# weft-microboard-0.net
KiCad netlist of a schematic drawn in EAGLE
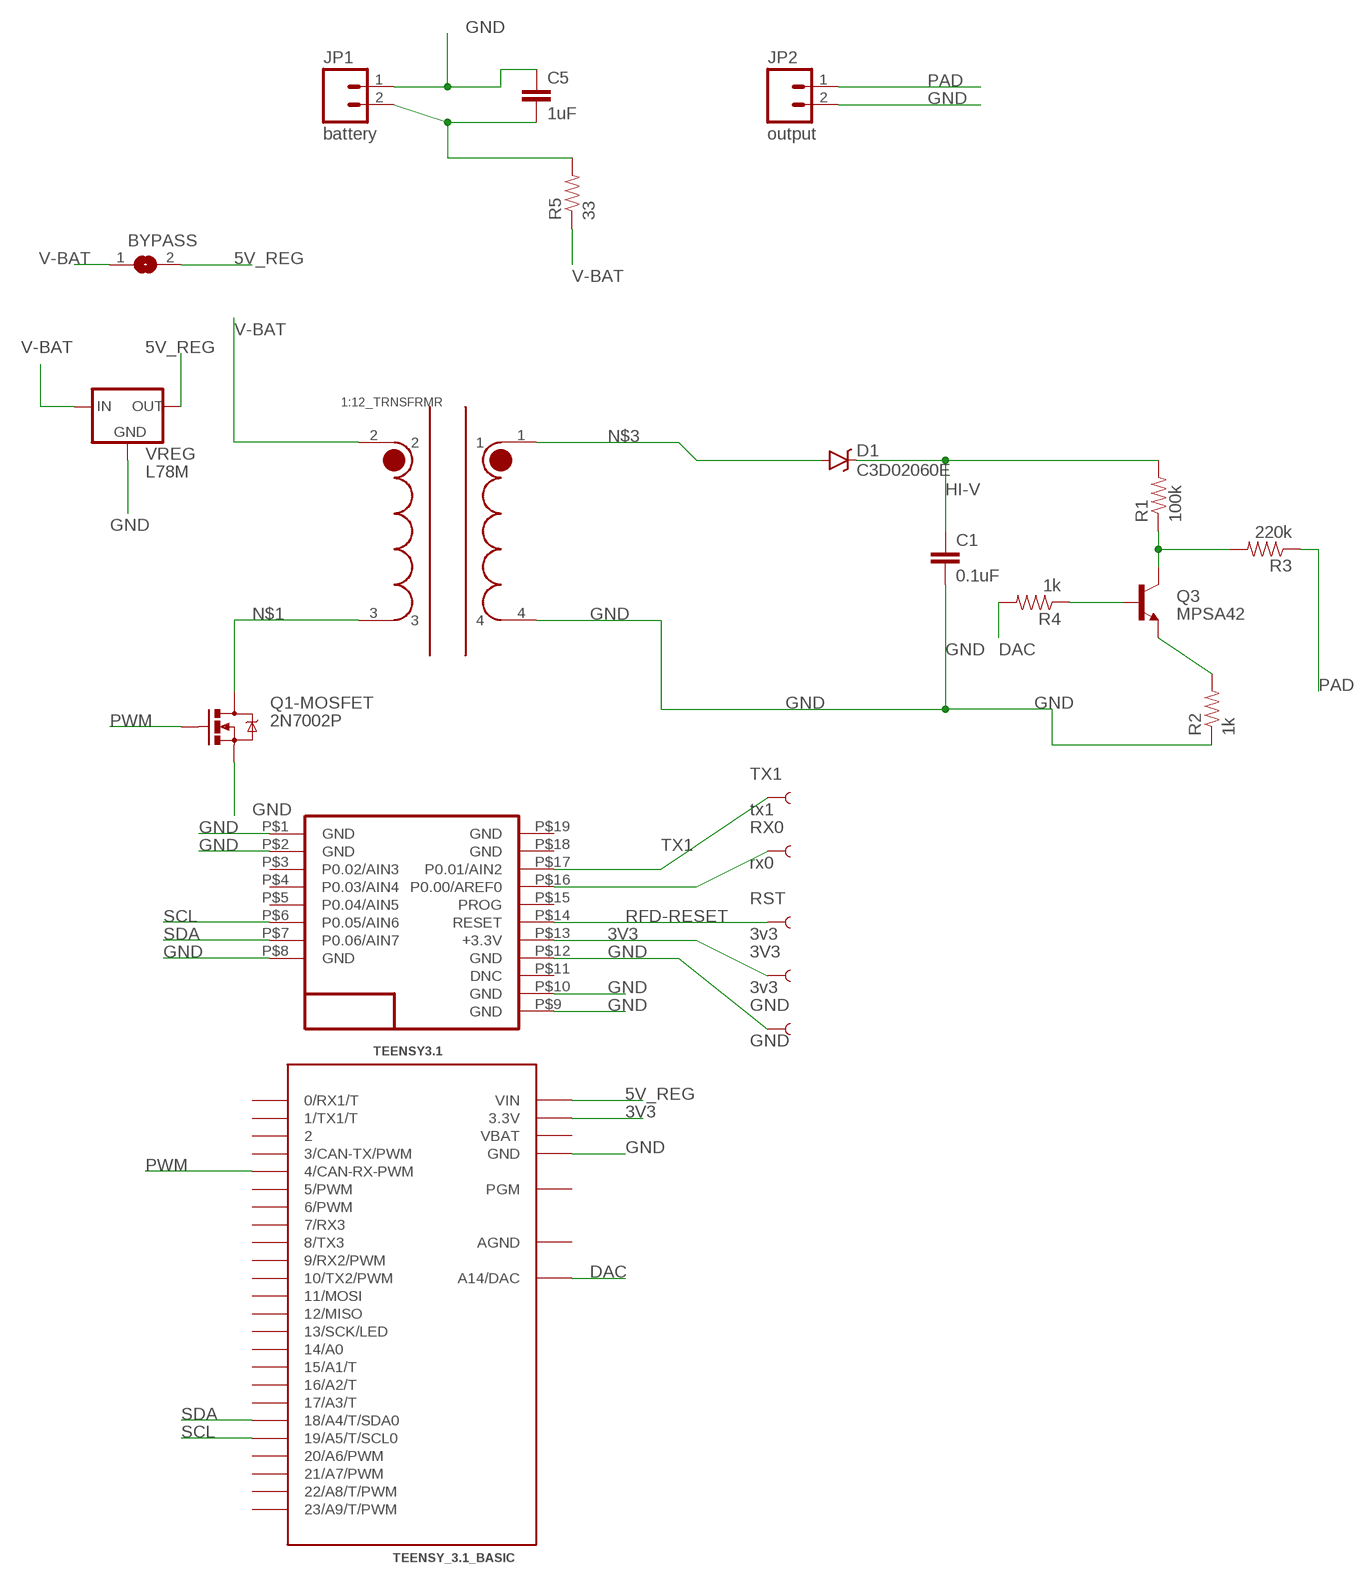
[diagram p0: schematic, sheet 1]

(export (version "E")
  (design (tool "Eeschema 10.0.6"))
  (components
    (comp (ref "1:12_TRNSFRMR")
      (value "PA0367")
      (footprint "eagle-import:PA0367")
      (libsource (lib "eagle-import") (part "PA0367"))
    )
    (comp (ref "3V3")
      (value "3v3")
      (footprint "eagle-import:PAD.03X.03")
      (libsource (lib "eagle-import") (part "TEST-POINT3"))
    )
    (comp (ref "BYPASS")
      (value "SJ")
      (footprint "eagle-import:SJ")
      (libsource (lib "eagle-import") (part "SJ"))
    )
    (comp (ref "C1")
      (value "0.1uF")
      (footprint "eagle-import:0805")
      (libsource (lib "eagle-import") (part "SparkFun-Passives_CAP0805"))
    )
    (comp (ref "C5")
      (value "1uF")
      (footprint "eagle-import:0805")
      (libsource (lib "eagle-import") (part "CAP0805"))
    )
    (comp (ref "D1")
      (value "C3D02060E")
      (footprint "eagle-import:TO252")
      (libsource (lib "eagle-import") (part "C3D02060E"))
    )
    (comp (ref "GND")
      (value "GND")
      (footprint "eagle-import:PAD.03X.03")
      (libsource (lib "eagle-import") (part "TEST-POINT3"))
    )
    (comp (ref "JP1")
      (value "battery")
      (footprint "eagle-import:JST-2-SMD")
      (libsource (lib "eagle-import") (part "M02-JST-2MM-SMT"))
    )
    (comp (ref "JP2")
      (value "output")
      (footprint "eagle-import:JST-2-SMD")
      (libsource (lib "eagle-import") (part "M02-JST-2MM-SMT"))
    )
    (comp (ref "Q1-MOSFET")
      (value "2N7002P")
      (footprint "eagle-import:SOT23-3")
      (libsource (lib "eagle-import") (part "MOSFET-NCHANNELBSS123LT1G"))
    )
    (comp (ref "Q3")
      (value "MPSA42")
      (footprint "eagle-import:SOT23-3")
      (libsource (lib "eagle-import") (part "TRANSISTOR_NPNMPSA42"))
    )
    (comp (ref "R1")
      (value "100k")
      (footprint "eagle-import:1206")
      (libsource (lib "eagle-import") (part "RESISTOR1206"))
    )
    (comp (ref "R2")
      (value "1k")
      (footprint "eagle-import:0805")
      (libsource (lib "eagle-import") (part "RESISTOR0805-RES"))
    )
    (comp (ref "R3")
      (value "220k")
      (footprint "eagle-import:1206")
      (libsource (lib "eagle-import") (part "RESISTOR1206"))
    )
    (comp (ref "R4")
      (value "1k")
      (footprint "eagle-import:0805")
      (libsource (lib "eagle-import") (part "RESISTOR0805-RES"))
    )
    (comp (ref "R5")
      (value "33")
      (footprint "eagle-import:0805")
      (libsource (lib "eagle-import") (part "RESISTOR0805-RES"))
    )
    (comp (ref "RFDUINO")
      (value "RFD22301")
      (footprint "eagle-import:RFD21733")
      (libsource (lib "eagle-import") (part "RFD22301"))
    )
    (comp (ref "RST")
      (value "3v3")
      (footprint "eagle-import:PAD.03X.03")
      (libsource (lib "eagle-import") (part "TEST-POINT3"))
    )
    (comp (ref "RX0")
      (value "rx0")
      (footprint "eagle-import:PAD.03X.03")
      (libsource (lib "eagle-import") (part "TEST-POINT3"))
    )
    (comp (ref "TEENSY3.1")
      (value "TEENSY_3.1_BASIC")
      (footprint "eagle-import:TEENSY_3.1_BASIC")
      (libsource (lib "eagle-import") (part "TEENSY_3.1_BASIC"))
    )
    (comp (ref "TX1")
      (value "tx1")
      (footprint "eagle-import:PAD.03X.03")
      (libsource (lib "eagle-import") (part "TEST-POINT3"))
    )
    (comp (ref "VREG")
      (value "L78M")
      (footprint "eagle-import:DPAK")
      (libsource (lib "eagle-import") (part "L78M"))
    )
  )
  (nets
    (net (code "1") (name "/3V3") (class "Default")
      (node (ref "3V3") (pin "P$1") (pinfunction "1_P$1") (pintype "bidirectional"))
      (node (ref "RFDUINO") (pin "P$13") (pinfunction "+3.3V_P$13") (pintype "bidirectional"))
      (node (ref "TEENSY3.1") (pin "3.3V") (pinfunction "3.3V_3.3V") (pintype "power_in"))
      (node (ref "TEENSY3.1") (pin "3.3V1") (pinfunction "3.3V_3.3V1") (pintype "power_in"))
    )
    (net (code "2") (name "/5V_REG") (class "Default")
      (node (ref "BYPASS") (pin "2") (pinfunction "2_2") (pintype "passive"))
      (node (ref "TEENSY3.1") (pin "VIN") (pinfunction "VIN_VIN") (pintype "power_in"))
      (node (ref "VREG") (pin "3") (pinfunction "OUT_3") (pintype "passive"))
    )
    (net (code "3") (name "/AGND") (class "Default")
      (node (ref "TEENSY3.1") (pin "AGND") (pinfunction "AGND_AGND") (pintype "power_in"))
    )
    (net (code "4") (name "/DAC") (class "Default")
      (node (ref "R4") (pin "2") (pinfunction "2_2") (pintype "passive"))
      (node (ref "TEENSY3.1") (pin "A14") (pinfunction "A14/DAC_A14") (pintype "bidirectional"))
    )
    (net (code "5") (name "/GND") (class "Default")
      (node (ref "1:12_TRNSFRMR") (pin "4") (pinfunction "4_4") (pintype "bidirectional"))
      (node (ref "C1") (pin "2") (pinfunction "2_2") (pintype "passive"))
      (node (ref "C5") (pin "1") (pinfunction "1_1") (pintype "passive"))
      (node (ref "GND") (pin "P$1") (pinfunction "1_P$1") (pintype "bidirectional"))
      (node (ref "JP1") (pin "1") (pinfunction "2_1") (pintype "passive"))
      (node (ref "JP2") (pin "2") (pinfunction "1_2") (pintype "passive"))
      (node (ref "Q1-MOSFET") (pin "2") (pinfunction "S_2") (pintype "passive"))
      (node (ref "R2") (pin "1") (pinfunction "1_1") (pintype "passive"))
      (node (ref "RFDUINO") (pin "P$1") (pinfunction "GND_P$1") (pintype "bidirectional"))
      (node (ref "RFDUINO") (pin "P$10") (pinfunction "GND_P$10") (pintype "bidirectional"))
      (node (ref "RFDUINO") (pin "P$12") (pinfunction "GND_P$12") (pintype "bidirectional"))
      (node (ref "RFDUINO") (pin "P$2") (pinfunction "GND_P$2") (pintype "bidirectional"))
      (node (ref "RFDUINO") (pin "P$8") (pinfunction "GND_P$8") (pintype "bidirectional"))
      (node (ref "RFDUINO") (pin "P$9") (pinfunction "GND_P$9") (pintype "bidirectional"))
      (node (ref "TEENSY3.1") (pin "GND") (pinfunction "GND_GND") (pintype "power_in"))
      (node (ref "TEENSY3.1") (pin "GND1") (pinfunction "GND_GND1") (pintype "power_in"))
      (node (ref "VREG") (pin "4") (pinfunction "GND_4") (pintype "input"))
    )
    (net (code "6") (name "/HI-V") (class "Default")
      (node (ref "C1") (pin "1") (pinfunction "1_1") (pintype "passive"))
      (node (ref "D1") (pin "1") (pinfunction "C_1") (pintype "passive"))
      (node (ref "R1") (pin "2") (pinfunction "2_2") (pintype "passive"))
    )
    (net (code "7") (name "/N$1") (class "Default")
      (node (ref "1:12_TRNSFRMR") (pin "3") (pinfunction "3_3") (pintype "bidirectional"))
      (node (ref "Q1-MOSFET") (pin "3") (pinfunction "D_3") (pintype "passive"))
    )
    (net (code "8") (name "/N$3") (class "Default")
      (node (ref "1:12_TRNSFRMR") (pin "1") (pinfunction "1_1") (pintype "bidirectional"))
      (node (ref "D1") (pin "2") (pinfunction "A_2") (pintype "passive"))
    )
    (net (code "9") (name "/PAD") (class "Default")
      (node (ref "JP2") (pin "1") (pinfunction "2_1") (pintype "passive"))
      (node (ref "R3") (pin "1") (pinfunction "1_1") (pintype "passive"))
    )
    (net (code "10") (name "/PWM") (class "Default")
      (node (ref "Q1-MOSFET") (pin "1") (pinfunction "G_1") (pintype "passive"))
      (node (ref "TEENSY3.1") (pin "4") (pinfunction "4/CAN-RX-PWM_4") (pintype "bidirectional"))
    )
    (net (code "11") (name "/RFD-RESET") (class "Default")
      (node (ref "RFDUINO") (pin "P$14") (pinfunction "RESET_P$14") (pintype "bidirectional"))
      (node (ref "RST") (pin "P$1") (pinfunction "1_P$1") (pintype "bidirectional"))
    )
    (net (code "12") (name "/SCL") (class "Default")
      (node (ref "RFDUINO") (pin "P$6") (pinfunction "P0.05/AIN6_P$6") (pintype "bidirectional"))
      (node (ref "TEENSY3.1") (pin "19/A5") (pinfunction "19/A5/T/SCL0_19/A5") (pintype "bidirectional"))
    )
    (net (code "13") (name "/SDA") (class "Default")
      (node (ref "RFDUINO") (pin "P$7") (pinfunction "P0.06/AIN7_P$7") (pintype "bidirectional"))
      (node (ref "TEENSY3.1") (pin "18/A4") (pinfunction "18/A4/T/SDA0_18/A4") (pintype "bidirectional"))
    )
    (net (code "14") (name "/TX1") (class "Default")
      (node (ref "RFDUINO") (pin "P$17") (pinfunction "P0.01/AIN2_P$17") (pintype "bidirectional"))
      (node (ref "TX1") (pin "P$1") (pinfunction "1_P$1") (pintype "bidirectional"))
    )
    (net (code "15") (name "/V-BAT") (class "Default")
      (node (ref "1:12_TRNSFRMR") (pin "2") (pinfunction "2_2") (pintype "bidirectional"))
      (node (ref "BYPASS") (pin "1") (pinfunction "1_1") (pintype "passive"))
      (node (ref "R5") (pin "1") (pinfunction "1_1") (pintype "passive"))
      (node (ref "VREG") (pin "1") (pinfunction "IN_1") (pintype "input"))
    )
    (net (code "16") (name "/VBAT") (class "Default")
      (node (ref "TEENSY3.1") (pin "VBAT") (pinfunction "VBAT_VBAT") (pintype "power_in"))
    )
    (net (code "17") (name "Net-(JP1-1)") (class "Default")
      (node (ref "C5") (pin "2") (pinfunction "2_2") (pintype "passive"))
      (node (ref "JP1") (pin "2") (pinfunction "1_2") (pintype "passive"))
      (node (ref "R5") (pin "2") (pinfunction "2_2") (pintype "passive"))
    )
    (net (code "18") (name "Net-(Q3-B)") (class "Default")
      (node (ref "Q3") (pin "1") (pinfunction "B_1") (pintype "passive"))
      (node (ref "R4") (pin "1") (pinfunction "1_1") (pintype "passive"))
    )
    (net (code "19") (name "Net-(Q3-C)") (class "Default")
      (node (ref "Q3") (pin "3") (pinfunction "C_3") (pintype "passive"))
      (node (ref "R1") (pin "1") (pinfunction "1_1") (pintype "passive"))
      (node (ref "R3") (pin "2") (pinfunction "2_2") (pintype "passive"))
    )
    (net (code "20") (name "Net-(Q3-E)") (class "Default")
      (node (ref "Q3") (pin "2") (pinfunction "E_2") (pintype "passive"))
      (node (ref "R2") (pin "2") (pinfunction "2_2") (pintype "passive"))
    )
    (net (code "21") (name "Net-(RFDUINO-P0.00{slash}AREF0)") (class "Default")
      (node (ref "RFDUINO") (pin "P$16") (pinfunction "P0.00/AREF0_P$16") (pintype "bidirectional"))
      (node (ref "RX0") (pin "P$1") (pinfunction "1_P$1") (pintype "bidirectional"))
    )
    (net (code "22") (name "unconnected-(RFDUINO-DNC-PadP$11)") (class "Default")
      (node (ref "RFDUINO") (pin "P$11") (pinfunction "DNC_P$11") (pintype "bidirectional"))
    )
    (net (code "23") (name "unconnected-(RFDUINO-GND-PadP$18)") (class "Default")
      (node (ref "RFDUINO") (pin "P$18") (pinfunction "GND_P$18") (pintype "bidirectional"))
    )
    (net (code "24") (name "unconnected-(RFDUINO-GND-PadP$19)") (class "Default")
      (node (ref "RFDUINO") (pin "P$19") (pinfunction "GND_P$19") (pintype "bidirectional"))
    )
    (net (code "25") (name "unconnected-(RFDUINO-P0.02{slash}AIN3-PadP$3)") (class "Default")
      (node (ref "RFDUINO") (pin "P$3") (pinfunction "P0.02/AIN3_P$3") (pintype "bidirectional"))
    )
    (net (code "26") (name "unconnected-(RFDUINO-P0.03{slash}AIN4-PadP$4)") (class "Default")
      (node (ref "RFDUINO") (pin "P$4") (pinfunction "P0.03/AIN4_P$4") (pintype "bidirectional"))
    )
    (net (code "27") (name "unconnected-(RFDUINO-P0.04{slash}AIN5-PadP$5)") (class "Default")
      (node (ref "RFDUINO") (pin "P$5") (pinfunction "P0.04/AIN5_P$5") (pintype "bidirectional"))
    )
    (net (code "28") (name "unconnected-(RFDUINO-PROG-PadP$15)") (class "Default")
      (node (ref "RFDUINO") (pin "P$15") (pinfunction "PROG_P$15") (pintype "bidirectional"))
    )
    (net (code "29") (name "unconnected-(TEENSY3.1-0{slash}RX1{slash}T-Pad0)") (class "Default")
      (node (ref "TEENSY3.1") (pin "0") (pinfunction "0/RX1/T_0") (pintype "bidirectional"))
    )
    (net (code "30") (name "unconnected-(TEENSY3.1-1{slash}TX1{slash}T-Pad1)") (class "Default")
      (node (ref "TEENSY3.1") (pin "1") (pinfunction "1/TX1/T_1") (pintype "bidirectional"))
    )
    (net (code "31") (name "unconnected-(TEENSY3.1-3{slash}CAN-TX{slash}PWM-Pad3)") (class "Default")
      (node (ref "TEENSY3.1") (pin "3") (pinfunction "3/CAN-TX/PWM_3") (pintype "bidirectional"))
    )
    (net (code "32") (name "unconnected-(TEENSY3.1-5{slash}PWM-Pad5)") (class "Default")
      (node (ref "TEENSY3.1") (pin "5") (pinfunction "5/PWM_5") (pintype "bidirectional"))
    )
    (net (code "33") (name "unconnected-(TEENSY3.1-6{slash}PWM-Pad6)") (class "Default")
      (node (ref "TEENSY3.1") (pin "6") (pinfunction "6/PWM_6") (pintype "bidirectional"))
    )
    (net (code "34") (name "unconnected-(TEENSY3.1-7{slash}RX3-Pad7)") (class "Default")
      (node (ref "TEENSY3.1") (pin "7") (pinfunction "7/RX3_7") (pintype "bidirectional"))
    )
    (net (code "35") (name "unconnected-(TEENSY3.1-8{slash}TX3-Pad8)") (class "Default")
      (node (ref "TEENSY3.1") (pin "8") (pinfunction "8/TX3_8") (pintype "bidirectional"))
    )
    (net (code "36") (name "unconnected-(TEENSY3.1-9{slash}RX2{slash}PWM-Pad9)") (class "Default")
      (node (ref "TEENSY3.1") (pin "9") (pinfunction "9/RX2/PWM_9") (pintype "bidirectional"))
    )
    (net (code "37") (name "unconnected-(TEENSY3.1-10{slash}TX2{slash}PWM-Pad10)") (class "Default")
      (node (ref "TEENSY3.1") (pin "10") (pinfunction "10/TX2/PWM_10") (pintype "bidirectional"))
    )
    (net (code "38") (name "unconnected-(TEENSY3.1-11{slash}MOSI-Pad11)") (class "Default")
      (node (ref "TEENSY3.1") (pin "11") (pinfunction "11/MOSI_11") (pintype "bidirectional"))
    )
    (net (code "39") (name "unconnected-(TEENSY3.1-12{slash}MISO-Pad12)") (class "Default")
      (node (ref "TEENSY3.1") (pin "12") (pinfunction "12/MISO_12") (pintype "bidirectional"))
    )
    (net (code "40") (name "unconnected-(TEENSY3.1-13{slash}SCK{slash}LED-Pad13)") (class "Default")
      (node (ref "TEENSY3.1") (pin "13") (pinfunction "13/SCK/LED_13") (pintype "bidirectional"))
    )
    (net (code "41") (name "unconnected-(TEENSY3.1-15{slash}A1{slash}T-Pad15{slash}A1)") (class "Default")
      (node (ref "TEENSY3.1") (pin "15/A1") (pinfunction "15/A1/T_15/A1") (pintype "bidirectional"))
    )
    (net (code "42") (name "unconnected-(TEENSY3.1-16{slash}A2{slash}T-Pad16{slash}A2)") (class "Default")
      (node (ref "TEENSY3.1") (pin "16/A2") (pinfunction "16/A2/T_16/A2") (pintype "bidirectional"))
    )
    (net (code "43") (name "unconnected-(TEENSY3.1-17{slash}A3{slash}T-Pad17{slash}A3)") (class "Default")
      (node (ref "TEENSY3.1") (pin "17/A3") (pinfunction "17/A3/T_17/A3") (pintype "bidirectional"))
    )
    (net (code "44") (name "unconnected-(TEENSY3.1-20{slash}A6{slash}PWM-Pad20{slash}A6)") (class "Default")
      (node (ref "TEENSY3.1") (pin "20/A6") (pinfunction "20/A6/PWM_20/A6") (pintype "bidirectional"))
    )
    (net (code "45") (name "unconnected-(TEENSY3.1-21{slash}A7{slash}PWM-Pad21{slash}A7)") (class "Default")
      (node (ref "TEENSY3.1") (pin "21/A7") (pinfunction "21/A7/PWM_21/A7") (pintype "bidirectional"))
    )
    (net (code "46") (name "unconnected-(TEENSY3.1-22{slash}A8{slash}T{slash}PWM-Pad22{slash}A8)") (class "Default")
      (node (ref "TEENSY3.1") (pin "22/A8") (pinfunction "22/A8/T/PWM_22/A8") (pintype "bidirectional"))
    )
    (net (code "47") (name "unconnected-(TEENSY3.1-23{slash}A9{slash}T{slash}PWM-Pad23{slash}A9)") (class "Default")
      (node (ref "TEENSY3.1") (pin "23/A9") (pinfunction "23/A9/T/PWM_23/A9") (pintype "bidirectional"))
    )
    (net (code "48") (name "unconnected-(TEENSY3.1-Pad2)") (class "Default")
      (node (ref "TEENSY3.1") (pin "2") (pinfunction "2_2") (pintype "bidirectional"))
    )
    (net (code "49") (name "unconnected-(TEENSY3.1-Pad14{slash}A0)") (class "Default")
      (node (ref "TEENSY3.1") (pin "14/A0") (pinfunction "14/A0_14/A0") (pintype "bidirectional"))
    )
    (net (code "50") (name "unconnected-(TEENSY3.1-PadPGM)") (class "Default")
      (node (ref "TEENSY3.1") (pin "PGM") (pinfunction "PGM_PGM") (pintype "bidirectional"))
    )
  )
)
